# ChargerV1_0.net
KiCad netlist of a schematic drawn in EAGLE
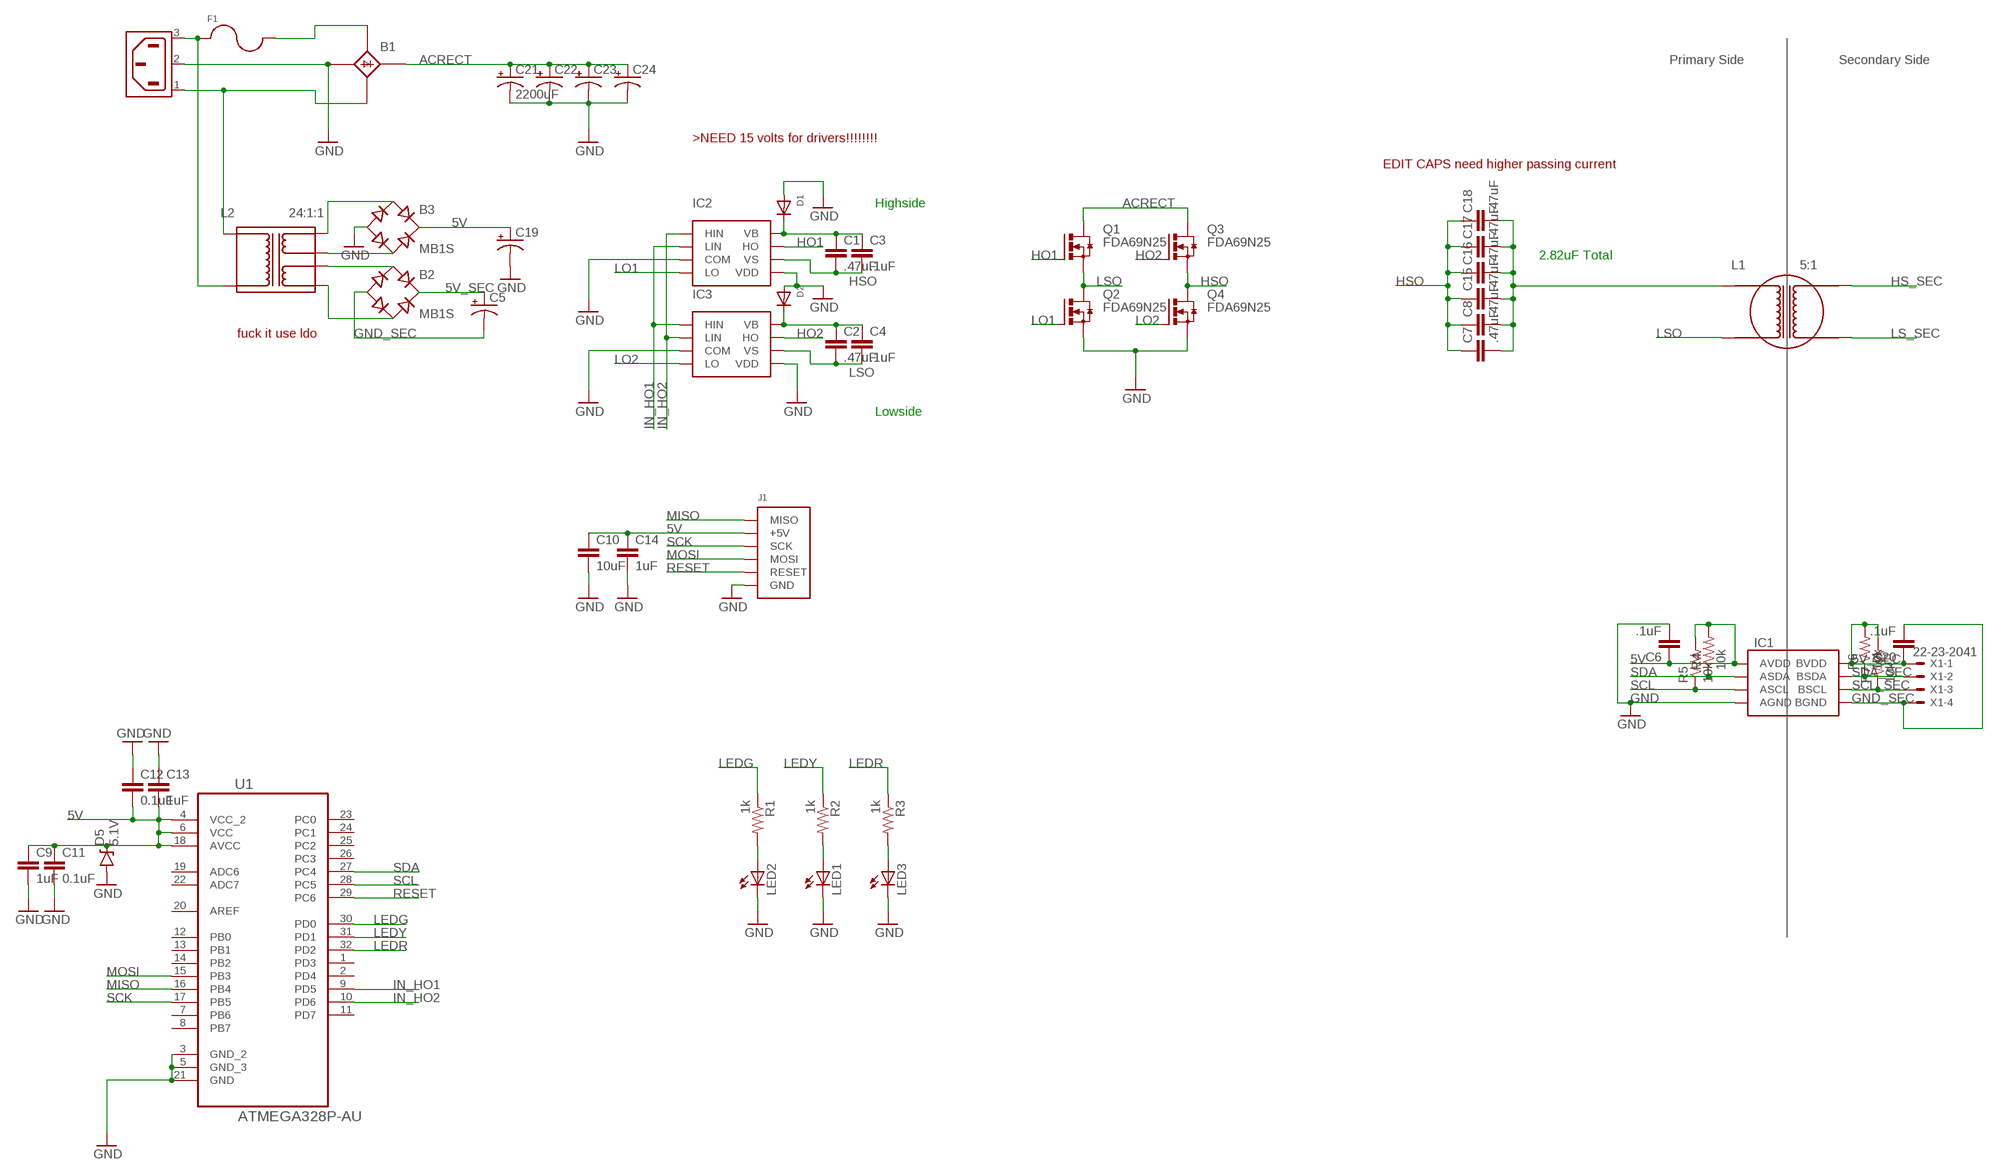
[diagram p0: schematic, sheet 1]

(export (version "E")
  (design (tool "Eeschema 10.0.6"))
  (components
    (comp (ref "B1")
      (value "B25A-")
      (footprint "eagle-import:B25A-")
      (libsource (lib "eagle-import") (part "B25A-"))
    )
    (comp (ref "B2")
      (value "MB1S")
      (footprint "eagle-import:SOIC-4")
      (libsource (lib "eagle-import") (part "MBS1"))
    )
    (comp (ref "B3")
      (value "MB1S")
      (footprint "eagle-import:SOIC-4")
      (libsource (lib "eagle-import") (part "MBS1"))
    )
    (comp (ref "C1")
      (value ".47uF")
      (footprint "eagle-import:C1206")
      (libsource (lib "eagle-import") (part "C-EUC1206"))
    )
    (comp (ref "C2")
      (value ".47uF")
      (footprint "eagle-import:C1206")
      (libsource (lib "eagle-import") (part "C-EUC1206"))
    )
    (comp (ref "C3")
      (value ".1uF")
      (footprint "eagle-import:C1206")
      (libsource (lib "eagle-import") (part "C-EUC1206"))
    )
    (comp (ref "C4")
      (value ".1uF")
      (footprint "eagle-import:C1206")
      (libsource (lib "eagle-import") (part "C-EUC1206"))
    )
    (comp (ref "C5")
      (value "CPOL-USE2.5-7")
      (footprint "eagle-import:E2,5-7")
      (libsource (lib "eagle-import") (part "CPOL-USE2.5-7"))
    )
    (comp (ref "C6")
      (value ".1uF")
      (footprint "eagle-import:0805-CAP")
      (libsource (lib "eagle-import") (part "10UF10V10%(0805)"))
    )
    (comp (ref "C7")
      (value ".47uF")
      (footprint "eagle-import:C1206")
      (libsource (lib "eagle-import") (part "C-EUC1206"))
    )
    (comp (ref "C8")
      (value ".47uF")
      (footprint "eagle-import:C1206")
      (libsource (lib "eagle-import") (part "C-EUC1206"))
    )
    (comp (ref "C9")
      (value "1uF")
      (footprint "eagle-import:0805-CAP")
      (libsource (lib "eagle-import") (part "0.33UF-50V-10%(0805)"))
    )
    (comp (ref "C10")
      (value "10uF")
      (footprint "eagle-import:0805-CAP")
      (libsource (lib "eagle-import") (part "10UF10V10%(0805)"))
    )
    (comp (ref "C11")
      (value "0.1uF")
      (footprint "eagle-import:0805-CAP")
      (libsource (lib "eagle-import") (part "0.33UF-50V-10%(0805)"))
    )
    (comp (ref "C12")
      (value "0.1uF")
      (footprint "eagle-import:0805-CAP")
      (libsource (lib "eagle-import") (part "0.33UF-50V-10%(0805)"))
    )
    (comp (ref "C13")
      (value "1uF")
      (footprint "eagle-import:0805-CAP")
      (libsource (lib "eagle-import") (part "0.33UF-50V-10%(0805)"))
    )
    (comp (ref "C14")
      (value "1uF")
      (footprint "eagle-import:0805-CAP")
      (libsource (lib "eagle-import") (part "0.33UF-50V-10%(0805)"))
    )
    (comp (ref "C15")
      (value ".47uF")
      (footprint "eagle-import:C1206")
      (libsource (lib "eagle-import") (part "C-EUC1206"))
    )
    (comp (ref "C16")
      (value ".47uF")
      (footprint "eagle-import:C1206")
      (libsource (lib "eagle-import") (part "C-EUC1206"))
    )
    (comp (ref "C17")
      (value ".47uF")
      (footprint "eagle-import:C1206")
      (libsource (lib "eagle-import") (part "C-EUC1206"))
    )
    (comp (ref "C18")
      (value ".47uF")
      (footprint "eagle-import:C1206")
      (libsource (lib "eagle-import") (part "C-EUC1206"))
    )
    (comp (ref "C19")
      (value "CPOL-USE2.5-7")
      (footprint "eagle-import:E2,5-7")
      (libsource (lib "eagle-import") (part "CPOL-USE2.5-7"))
    )
    (comp (ref "C20")
      (value ".1uF")
      (footprint "eagle-import:0805-CAP")
      (libsource (lib "eagle-import") (part "10UF10V10%(0805)"))
    )
    (comp (ref "C21")
      (value "2200uF")
      (footprint "eagle-import:EB30D")
      (libsource (lib "eagle-import") (part "CPOL-USE10-30"))
    )
    (comp (ref "C22")
      (value "CPOL-USE10-30")
      (footprint "eagle-import:EB30D")
      (libsource (lib "eagle-import") (part "CPOL-USE10-30"))
    )
    (comp (ref "C23")
      (value "CPOL-USE10-30")
      (footprint "eagle-import:EB30D")
      (libsource (lib "eagle-import") (part "CPOL-USE10-30"))
    )
    (comp (ref "C24")
      (value "CPOL-USE10-30")
      (footprint "eagle-import:EB30D")
      (libsource (lib "eagle-import") (part "CPOL-USE10-30"))
    )
    (comp (ref "D1")
      (value "DIODESMA")
      (footprint "eagle-import:SMADIODE")
      (libsource (lib "eagle-import") (part "DIODESMA"))
    )
    (comp (ref "D2")
      (value "DIODESMA")
      (footprint "eagle-import:SMADIODE")
      (libsource (lib "eagle-import") (part "DIODESMA"))
    )
    (comp (ref "D5")
      (value "5.1V")
      (footprint "eagle-import:SOD-323")
      (libsource (lib "eagle-import") (part "DIODE-ZENER5.6V"))
    )
    (comp (ref "F1")
      (value "FUSE")
      (footprint "eagle-import:FUSE_HOLDER")
      (libsource (lib "eagle-import") (part "FUSE"))
    )
    (comp (ref "IC1")
      (value "SI8600_DUALCHANNELISO")
      (footprint "eagle-import:SOIC-8")
      (libsource (lib "eagle-import") (part "SI8600_DUALCHANNELISO"))
    )
    (comp (ref "IC2")
      (value "FAN7190")
      (footprint "eagle-import:SOIC-8")
      (libsource (lib "eagle-import") (part "FAN7190"))
    )
    (comp (ref "IC3")
      (value "FAN7190")
      (footprint "eagle-import:SOIC-8")
      (libsource (lib "eagle-import") (part "FAN7190"))
    )
    (comp (ref "J1")
      (value "ISPHEADER")
      (footprint "eagle-import:2X3PIN_.1'")
      (libsource (lib "eagle-import") (part "ISPHEADER"))
    )
    (comp (ref "L1")
      (value "5:1")
      (footprint "eagle-import:TRANSFORMER_TOR_CUSTOM")
      (libsource (lib "eagle-import") (part "TRANSFORMER"))
    )
    (comp (ref "L2")
      (value "24:1:1")
      (footprint "eagle-import:TRANSFORMER_CUSTOM1")
      (libsource (lib "eagle-import") (part "TRANSFORMER1{colon}2"))
    )
    (comp (ref "LED1")
      (value "LEDCHIPLED_0805")
      (footprint "eagle-import:CHIPLED_0805")
      (libsource (lib "eagle-import") (part "LEDCHIPLED_0805"))
    )
    (comp (ref "LED2")
      (value "LEDCHIPLED_0805")
      (footprint "eagle-import:CHIPLED_0805")
      (libsource (lib "eagle-import") (part "LEDCHIPLED_0805"))
    )
    (comp (ref "LED3")
      (value "LEDCHIPLED_0805")
      (footprint "eagle-import:CHIPLED_0805")
      (libsource (lib "eagle-import") (part "LEDCHIPLED_0805"))
    )
    (comp (ref "Q1")
      (value "FDA69N25")
      (footprint "eagle-import:TO247BV")
      (libsource (lib "eagle-import") (part "IRFP240"))
    )
    (comp (ref "Q2")
      (value "FDA69N25")
      (footprint "eagle-import:TO247BV")
      (libsource (lib "eagle-import") (part "IRFP240"))
    )
    (comp (ref "Q3")
      (value "FDA69N25")
      (footprint "eagle-import:TO247BV")
      (libsource (lib "eagle-import") (part "IRFP240"))
    )
    (comp (ref "Q4")
      (value "FDA69N25")
      (footprint "eagle-import:TO247BV")
      (libsource (lib "eagle-import") (part "IRFP240"))
    )
    (comp (ref "R1")
      (value "1k")
      (footprint "eagle-import:0805")
      (libsource (lib "eagle-import") (part "0.3OHM-1/8W-1%(0805)"))
    )
    (comp (ref "R2")
      (value "1k")
      (footprint "eagle-import:0805")
      (libsource (lib "eagle-import") (part "0.3OHM-1/8W-1%(0805)"))
    )
    (comp (ref "R3")
      (value "1k")
      (footprint "eagle-import:0805")
      (libsource (lib "eagle-import") (part "0.3OHM-1/8W-1%(0805)"))
    )
    (comp (ref "R4")
      (value "10k")
      (footprint "eagle-import:0805")
      (libsource (lib "eagle-import") (part "0.3OHM-1/8W-1%(0805)"))
    )
    (comp (ref "R5")
      (value "10k")
      (footprint "eagle-import:0805")
      (libsource (lib "eagle-import") (part "0.3OHM-1/8W-1%(0805)"))
    )
    (comp (ref "R6")
      (value "10k")
      (footprint "eagle-import:0805")
      (libsource (lib "eagle-import") (part "0.3OHM-1/8W-1%(0805)"))
    )
    (comp (ref "R7")
      (value "10k")
      (footprint "eagle-import:0805")
      (libsource (lib "eagle-import") (part "0.3OHM-1/8W-1%(0805)"))
    )
    (comp (ref "U1")
      (value "ATMEGA328P-AU")
      (footprint "eagle-import:QFP80P900X900X120-32N")
      (libsource (lib "eagle-import") (part "ATMEGA328P-AU"))
    )
    (comp (ref "X1")
      (value "22-23-2041")
      (footprint "eagle-import:22-23-2041")
      (fields (field (name "MF") "MOLEX"))
      (libsource (lib "eagle-import") (part "22-23-2041"))
    )
    (comp (ref "X2")
      (value "6ESRM-P")
      (footprint "eagle-import:6ESRM-P")
      (fields (field (name "MF") "TYCO ELECTRONICS"))
      (libsource (lib "eagle-import") (part "6ESRM-P"))
    )
  )
  (nets
    (net (code "1") (name "/5V") (class "Default")
      (node (ref "B3") (pin "+") (pinfunction "+_+") (pintype "passive"))
      (node (ref "C10") (pin "1") (pinfunction "1_1") (pintype "passive"))
      (node (ref "C11") (pin "1") (pinfunction "1_1") (pintype "passive"))
      (node (ref "C12") (pin "2") (pinfunction "2_2") (pintype "passive"))
      (node (ref "C13") (pin "2") (pinfunction "2_2") (pintype "passive"))
      (node (ref "C14") (pin "1") (pinfunction "1_1") (pintype "passive"))
      (node (ref "C19") (pin "+") (pinfunction "+_+") (pintype "passive"))
      (node (ref "C6") (pin "1") (pinfunction "1_1") (pintype "passive"))
      (node (ref "C9") (pin "1") (pinfunction "1_1") (pintype "passive"))
      (node (ref "D5") (pin "C") (pinfunction "C_C") (pintype "passive"))
      (node (ref "IC1") (pin "P$1") (pinfunction "AVDD_P$1") (pintype "bidirectional"))
      (node (ref "J1") (pin "P$2") (pinfunction "+5V_P$2") (pintype "bidirectional"))
      (node (ref "R4") (pin "2") (pinfunction "2_2") (pintype "passive"))
      (node (ref "R5") (pin "2") (pinfunction "2_2") (pintype "passive"))
      (node (ref "U1") (pin "18") (pinfunction "AVCC_18") (pintype "power_in"))
      (node (ref "U1") (pin "4") (pinfunction "VCC_2_4") (pintype "power_in"))
      (node (ref "U1") (pin "6") (pinfunction "VCC_6") (pintype "power_in"))
    )
    (net (code "2") (name "/5V_SEC") (class "Default")
      (node (ref "B2") (pin "+") (pinfunction "+_+") (pintype "passive"))
      (node (ref "C20") (pin "1") (pinfunction "1_1") (pintype "passive"))
      (node (ref "C5") (pin "+") (pinfunction "+_+") (pintype "passive"))
      (node (ref "IC1") (pin "P$8") (pinfunction "BVDD_P$8") (pintype "bidirectional"))
      (node (ref "R6") (pin "2") (pinfunction "2_2") (pintype "passive"))
      (node (ref "R7") (pin "2") (pinfunction "2_2") (pintype "passive"))
      (node (ref "X1") (pin "1") (pinfunction "S_1") (pintype "passive"))
    )
    (net (code "3") (name "/ACRECT") (class "Default")
      (node (ref "B1") (pin "+1") (pinfunction "+_+1") (pintype "passive"))
      (node (ref "C21") (pin "+") (pinfunction "+_+") (pintype "passive"))
      (node (ref "C22") (pin "+") (pinfunction "+_+") (pintype "passive"))
      (node (ref "C23") (pin "+") (pinfunction "+_+") (pintype "passive"))
      (node (ref "C24") (pin "+") (pinfunction "+_+") (pintype "passive"))
      (node (ref "Q1") (pin "D") (pinfunction "D_D") (pintype "passive"))
      (node (ref "Q3") (pin "D") (pinfunction "D_D") (pintype "passive"))
    )
    (net (code "4") (name "/GND_SEC") (class "Default")
      (node (ref "B2") (pin "-") (pinfunction "-_-") (pintype "passive"))
      (node (ref "C20") (pin "2") (pinfunction "2_2") (pintype "passive"))
      (node (ref "C5") (pin "-") (pinfunction "-_-") (pintype "passive"))
      (node (ref "IC1") (pin "P$5") (pinfunction "BGND_P$5") (pintype "bidirectional"))
      (node (ref "X1") (pin "4") (pinfunction "S_4") (pintype "passive"))
    )
    (net (code "5") (name "/HO1") (class "Default")
      (node (ref "IC2") (pin "P$7") (pinfunction "HO_P$7") (pintype "bidirectional"))
      (node (ref "Q1") (pin "G") (pinfunction "G_G") (pintype "passive"))
    )
    (net (code "6") (name "/HO2") (class "Default")
      (node (ref "IC3") (pin "P$7") (pinfunction "HO_P$7") (pintype "bidirectional"))
      (node (ref "Q3") (pin "G") (pinfunction "G_G") (pintype "passive"))
    )
    (net (code "7") (name "/HSO") (class "Default")
      (node (ref "C1") (pin "2") (pinfunction "2_2") (pintype "passive"))
      (node (ref "C15") (pin "1") (pinfunction "1_1") (pintype "passive"))
      (node (ref "C16") (pin "1") (pinfunction "1_1") (pintype "passive"))
      (node (ref "C17") (pin "1") (pinfunction "1_1") (pintype "passive"))
      (node (ref "C18") (pin "1") (pinfunction "1_1") (pintype "passive"))
      (node (ref "C3") (pin "2") (pinfunction "2_2") (pintype "passive"))
      (node (ref "C7") (pin "1") (pinfunction "1_1") (pintype "passive"))
      (node (ref "C8") (pin "1") (pinfunction "1_1") (pintype "passive"))
      (node (ref "IC2") (pin "P$6") (pinfunction "VS_P$6") (pintype "bidirectional"))
      (node (ref "Q3") (pin "S") (pinfunction "S_S") (pintype "passive"))
      (node (ref "Q4") (pin "D") (pinfunction "D_D") (pintype "passive"))
    )
    (net (code "8") (name "/HS_SEC") (class "Default")
      (node (ref "L1") (pin "P$4") (pinfunction "P$4_P$4") (pintype "bidirectional"))
    )
    (net (code "9") (name "/IN_HO1") (class "Default")
      (node (ref "IC2") (pin "P$2") (pinfunction "LIN_P$2") (pintype "bidirectional"))
      (node (ref "IC3") (pin "P$1") (pinfunction "HIN_P$1") (pintype "bidirectional"))
      (node (ref "U1") (pin "9") (pinfunction "PD5_9") (pintype "bidirectional"))
    )
    (net (code "10") (name "/IN_HO2") (class "Default")
      (node (ref "IC2") (pin "P$1") (pinfunction "HIN_P$1") (pintype "bidirectional"))
      (node (ref "IC3") (pin "P$2") (pinfunction "LIN_P$2") (pintype "bidirectional"))
      (node (ref "U1") (pin "10") (pinfunction "PD6_10") (pintype "bidirectional"))
    )
    (net (code "11") (name "/LEDG") (class "Default")
      (node (ref "R1") (pin "1") (pinfunction "1_1") (pintype "passive"))
      (node (ref "U1") (pin "30") (pinfunction "PD0_30") (pintype "bidirectional"))
    )
    (net (code "12") (name "/LEDR") (class "Default")
      (node (ref "R3") (pin "1") (pinfunction "1_1") (pintype "passive"))
      (node (ref "U1") (pin "32") (pinfunction "PD2_32") (pintype "bidirectional"))
    )
    (net (code "13") (name "/LEDY") (class "Default")
      (node (ref "R2") (pin "1") (pinfunction "1_1") (pintype "passive"))
      (node (ref "U1") (pin "31") (pinfunction "PD1_31") (pintype "bidirectional"))
    )
    (net (code "14") (name "/LO1") (class "Default")
      (node (ref "IC2") (pin "P$4") (pinfunction "LO_P$4") (pintype "bidirectional"))
      (node (ref "Q2") (pin "G") (pinfunction "G_G") (pintype "passive"))
    )
    (net (code "15") (name "/LO2") (class "Default")
      (node (ref "IC3") (pin "P$4") (pinfunction "LO_P$4") (pintype "bidirectional"))
      (node (ref "Q4") (pin "G") (pinfunction "G_G") (pintype "passive"))
    )
    (net (code "16") (name "/LSO") (class "Default")
      (node (ref "C2") (pin "2") (pinfunction "2_2") (pintype "passive"))
      (node (ref "C4") (pin "2") (pinfunction "2_2") (pintype "passive"))
      (node (ref "IC3") (pin "P$6") (pinfunction "VS_P$6") (pintype "bidirectional"))
      (node (ref "L1") (pin "P$2") (pinfunction "P$2_P$2") (pintype "bidirectional"))
      (node (ref "Q1") (pin "S") (pinfunction "S_S") (pintype "passive"))
      (node (ref "Q2") (pin "D") (pinfunction "D_D") (pintype "passive"))
    )
    (net (code "17") (name "/LS_SEC") (class "Default")
      (node (ref "L1") (pin "P$3") (pinfunction "P$3_P$3") (pintype "bidirectional"))
    )
    (net (code "18") (name "/MISO") (class "Default")
      (node (ref "J1") (pin "P$1") (pinfunction "MISO_P$1") (pintype "bidirectional"))
      (node (ref "U1") (pin "16") (pinfunction "PB4_16") (pintype "bidirectional"))
    )
    (net (code "19") (name "/MOSI") (class "Default")
      (node (ref "J1") (pin "P$4") (pinfunction "MOSI_P$4") (pintype "bidirectional"))
      (node (ref "U1") (pin "15") (pinfunction "PB3_15") (pintype "bidirectional"))
    )
    (net (code "20") (name "/RESET") (class "Default")
      (node (ref "J1") (pin "P$5") (pinfunction "RESET_P$5") (pintype "bidirectional"))
      (node (ref "U1") (pin "29") (pinfunction "PC6_29") (pintype "bidirectional"))
    )
    (net (code "21") (name "/SCK") (class "Default")
      (node (ref "J1") (pin "P$3") (pinfunction "SCK_P$3") (pintype "bidirectional"))
      (node (ref "U1") (pin "17") (pinfunction "PB5_17") (pintype "bidirectional"))
    )
    (net (code "22") (name "/SCL") (class "Default")
      (node (ref "IC1") (pin "P$3") (pinfunction "ASCL_P$3") (pintype "bidirectional"))
      (node (ref "R5") (pin "1") (pinfunction "1_1") (pintype "passive"))
      (node (ref "U1") (pin "28") (pinfunction "PC5_28") (pintype "bidirectional"))
    )
    (net (code "23") (name "/SCL_SEC") (class "Default")
      (node (ref "IC1") (pin "P$6") (pinfunction "BSCL_P$6") (pintype "bidirectional"))
      (node (ref "R7") (pin "1") (pinfunction "1_1") (pintype "passive"))
      (node (ref "X1") (pin "3") (pinfunction "S_3") (pintype "passive"))
    )
    (net (code "24") (name "/SDA") (class "Default")
      (node (ref "IC1") (pin "P$2") (pinfunction "ASDA_P$2") (pintype "bidirectional"))
      (node (ref "R4") (pin "1") (pinfunction "1_1") (pintype "passive"))
      (node (ref "U1") (pin "27") (pinfunction "PC4_27") (pintype "bidirectional"))
    )
    (net (code "25") (name "/SDA_SEC") (class "Default")
      (node (ref "IC1") (pin "P$7") (pinfunction "BSDA_P$7") (pintype "bidirectional"))
      (node (ref "R6") (pin "1") (pinfunction "1_1") (pintype "passive"))
      (node (ref "X1") (pin "2") (pinfunction "S_2") (pintype "passive"))
    )
    (net (code "26") (name "GND") (class "Default")
      (node (ref "B1") (pin "-1") (pinfunction "-_-1") (pintype "passive"))
      (node (ref "B3") (pin "-") (pinfunction "-_-") (pintype "passive"))
      (node (ref "C10") (pin "2") (pinfunction "2_2") (pintype "passive"))
      (node (ref "C11") (pin "2") (pinfunction "2_2") (pintype "passive"))
      (node (ref "C12") (pin "1") (pinfunction "1_1") (pintype "passive"))
      (node (ref "C13") (pin "1") (pinfunction "1_1") (pintype "passive"))
      (node (ref "C14") (pin "2") (pinfunction "2_2") (pintype "passive"))
      (node (ref "C19") (pin "-") (pinfunction "-_-") (pintype "passive"))
      (node (ref "C21") (pin "-") (pinfunction "-_-") (pintype "passive"))
      (node (ref "C22") (pin "-") (pinfunction "-_-") (pintype "passive"))
      (node (ref "C23") (pin "-") (pinfunction "-_-") (pintype "passive"))
      (node (ref "C24") (pin "-") (pinfunction "-_-") (pintype "passive"))
      (node (ref "C6") (pin "2") (pinfunction "2_2") (pintype "passive"))
      (node (ref "C9") (pin "2") (pinfunction "2_2") (pintype "passive"))
      (node (ref "D1") (pin "A") (pinfunction "A_A") (pintype "passive"))
      (node (ref "D2") (pin "A") (pinfunction "A_A") (pintype "passive"))
      (node (ref "D5") (pin "A") (pinfunction "A_A") (pintype "passive"))
      (node (ref "IC1") (pin "P$4") (pinfunction "AGND_P$4") (pintype "bidirectional"))
      (node (ref "IC2") (pin "P$3") (pinfunction "COM_P$3") (pintype "bidirectional"))
      (node (ref "IC2") (pin "P$5") (pinfunction "VDD_P$5") (pintype "bidirectional"))
      (node (ref "IC3") (pin "P$3") (pinfunction "COM_P$3") (pintype "bidirectional"))
      (node (ref "IC3") (pin "P$5") (pinfunction "VDD_P$5") (pintype "bidirectional"))
      (node (ref "J1") (pin "P$6") (pinfunction "GND_P$6") (pintype "bidirectional"))
      (node (ref "LED1") (pin "C") (pinfunction "C_C") (pintype "passive"))
      (node (ref "LED2") (pin "C") (pinfunction "C_C") (pintype "passive"))
      (node (ref "LED3") (pin "C") (pinfunction "C_C") (pintype "passive"))
      (node (ref "Q2") (pin "S") (pinfunction "S_S") (pintype "passive"))
      (node (ref "Q4") (pin "S") (pinfunction "S_S") (pintype "passive"))
      (node (ref "U1") (pin "21") (pinfunction "GND_21") (pintype "passive"))
      (node (ref "U1") (pin "3") (pinfunction "GND_2_3") (pintype "passive"))
      (node (ref "U1") (pin "5") (pinfunction "GND_3_5") (pintype "passive"))
      (node (ref "X2") (pin "2") (pinfunction "SH_2") (pintype "passive"))
    )
    (net (code "27") (name "Net-(B1-AC1-PadAC1-)") (class "Default")
      (node (ref "B1") (pin "AC1-") (pinfunction "AC1_AC1-") (pintype "passive"))
      (node (ref "F1") (pin "P$3") (pinfunction "P$2_P$3") (pintype "bidirectional"))
      (node (ref "F1") (pin "P$4") (pinfunction "P$2_P$4") (pintype "bidirectional"))
    )
    (net (code "28") (name "Net-(B2-AC1)") (class "Default")
      (node (ref "B2") (pin "~1") (pinfunction "AC1_~1") (pintype "passive"))
      (node (ref "L2") (pin "OUT21") (pinfunction "OUT21_OUT21") (pintype "bidirectional"))
    )
    (net (code "29") (name "Net-(B2-AC2)") (class "Default")
      (node (ref "B2") (pin "~2") (pinfunction "AC2_~2") (pintype "passive"))
      (node (ref "L2") (pin "OUT22") (pinfunction "OUT22_OUT22") (pintype "bidirectional"))
    )
    (net (code "30") (name "Net-(B3-AC1)") (class "Default")
      (node (ref "B3") (pin "~1") (pinfunction "AC1_~1") (pintype "passive"))
      (node (ref "L2") (pin "OUT11") (pinfunction "OUT11_OUT11") (pintype "bidirectional"))
    )
    (net (code "31") (name "Net-(B3-AC2)") (class "Default")
      (node (ref "B3") (pin "~2") (pinfunction "AC2_~2") (pintype "passive"))
      (node (ref "L2") (pin "OUT12") (pinfunction "OUT12_OUT12") (pintype "bidirectional"))
    )
    (net (code "32") (name "Net-(C15-Pad2)") (class "Default")
      (node (ref "C15") (pin "2") (pinfunction "2_2") (pintype "passive"))
      (node (ref "C16") (pin "2") (pinfunction "2_2") (pintype "passive"))
      (node (ref "C17") (pin "2") (pinfunction "2_2") (pintype "passive"))
      (node (ref "C18") (pin "2") (pinfunction "2_2") (pintype "passive"))
      (node (ref "C7") (pin "2") (pinfunction "2_2") (pintype "passive"))
      (node (ref "C8") (pin "2") (pinfunction "2_2") (pintype "passive"))
      (node (ref "L1") (pin "P$1") (pinfunction "P$1_P$1") (pintype "bidirectional"))
    )
    (net (code "33") (name "Net-(IC2-VB)") (class "Default")
      (node (ref "C1") (pin "1") (pinfunction "1_1") (pintype "passive"))
      (node (ref "C3") (pin "1") (pinfunction "1_1") (pintype "passive"))
      (node (ref "D1") (pin "C") (pinfunction "C_C") (pintype "passive"))
      (node (ref "IC2") (pin "P$8") (pinfunction "VB_P$8") (pintype "bidirectional"))
    )
    (net (code "34") (name "Net-(IC3-VB)") (class "Default")
      (node (ref "C2") (pin "1") (pinfunction "1_1") (pintype "passive"))
      (node (ref "C4") (pin "1") (pinfunction "1_1") (pintype "passive"))
      (node (ref "D2") (pin "C") (pinfunction "C_C") (pintype "passive"))
      (node (ref "IC3") (pin "P$8") (pinfunction "VB_P$8") (pintype "bidirectional"))
    )
    (net (code "35") (name "Net-(LED1-PadA)") (class "Default")
      (node (ref "LED1") (pin "A") (pinfunction "A_A") (pintype "passive"))
      (node (ref "R2") (pin "2") (pinfunction "2_2") (pintype "passive"))
    )
    (net (code "36") (name "Net-(LED2-PadA)") (class "Default")
      (node (ref "LED2") (pin "A") (pinfunction "A_A") (pintype "passive"))
      (node (ref "R1") (pin "2") (pinfunction "2_2") (pintype "passive"))
    )
    (net (code "37") (name "Net-(LED3-PadA)") (class "Default")
      (node (ref "LED3") (pin "A") (pinfunction "A_A") (pintype "passive"))
      (node (ref "R3") (pin "2") (pinfunction "2_2") (pintype "passive"))
    )
    (net (code "38") (name "Net-(X2-AC1)") (class "Default")
      (node (ref "B1") (pin "AC2-") (pinfunction "AC2_AC2-") (pintype "passive"))
      (node (ref "L2") (pin "IN1") (pinfunction "IN1_IN1") (pintype "bidirectional"))
      (node (ref "X2") (pin "1") (pinfunction "AC1_1") (pintype "passive"))
    )
    (net (code "39") (name "Net-(X2-AC2)") (class "Default")
      (node (ref "F1") (pin "P$1") (pinfunction "P$1_P$1") (pintype "bidirectional"))
      (node (ref "F1") (pin "P$2") (pinfunction "P$1_P$2") (pintype "bidirectional"))
      (node (ref "L2") (pin "IN2") (pinfunction "IN2_IN2") (pintype "bidirectional"))
      (node (ref "X2") (pin "3") (pinfunction "AC2_3") (pintype "passive"))
    )
    (net (code "40") (name "unconnected-(B1-Pad+)") (class "Default")
      (node (ref "B1") (pin "+") (pinfunction "+_+") (pintype "passive"))
    )
    (net (code "41") (name "unconnected-(B1-Pad-)") (class "Default")
      (node (ref "B1") (pin "-") (pinfunction "-_-") (pintype "passive"))
    )
    (net (code "42") (name "unconnected-(B1-PadAC1)") (class "Default")
      (node (ref "B1") (pin "AC1") (pinfunction "AC1_AC1") (pintype "passive"))
    )
    (net (code "43") (name "unconnected-(B1-PadAC2)") (class "Default")
      (node (ref "B1") (pin "AC2") (pinfunction "AC2_AC2") (pintype "passive"))
    )
    (net (code "44") (name "unconnected-(U1-ADC6-Pad19)") (class "Default")
      (node (ref "U1") (pin "19") (pinfunction "ADC6_19") (pintype "input"))
    )
    (net (code "45") (name "unconnected-(U1-ADC7-Pad22)") (class "Default")
      (node (ref "U1") (pin "22") (pinfunction "ADC7_22") (pintype "input"))
    )
    (net (code "46") (name "unconnected-(U1-AREF-Pad20)") (class "Default")
      (node (ref "U1") (pin "20") (pinfunction "AREF_20") (pintype "input"))
    )
    (net (code "47") (name "unconnected-(U1-PB0-Pad12)") (class "Default")
      (node (ref "U1") (pin "12") (pinfunction "PB0_12") (pintype "bidirectional"))
    )
    (net (code "48") (name "unconnected-(U1-PB1-Pad13)") (class "Default")
      (node (ref "U1") (pin "13") (pinfunction "PB1_13") (pintype "bidirectional"))
    )
    (net (code "49") (name "unconnected-(U1-PB2-Pad14)") (class "Default")
      (node (ref "U1") (pin "14") (pinfunction "PB2_14") (pintype "bidirectional"))
    )
    (net (code "50") (name "unconnected-(U1-PB6-Pad7)") (class "Default")
      (node (ref "U1") (pin "7") (pinfunction "PB6_7") (pintype "bidirectional"))
    )
    (net (code "51") (name "unconnected-(U1-PB7-Pad8)") (class "Default")
      (node (ref "U1") (pin "8") (pinfunction "PB7_8") (pintype "bidirectional"))
    )
    (net (code "52") (name "unconnected-(U1-PC0-Pad23)") (class "Default")
      (node (ref "U1") (pin "23") (pinfunction "PC0_23") (pintype "bidirectional"))
    )
    (net (code "53") (name "unconnected-(U1-PC1-Pad24)") (class "Default")
      (node (ref "U1") (pin "24") (pinfunction "PC1_24") (pintype "bidirectional"))
    )
    (net (code "54") (name "unconnected-(U1-PC2-Pad25)") (class "Default")
      (node (ref "U1") (pin "25") (pinfunction "PC2_25") (pintype "bidirectional"))
    )
    (net (code "55") (name "unconnected-(U1-PC3-Pad26)") (class "Default")
      (node (ref "U1") (pin "26") (pinfunction "PC3_26") (pintype "bidirectional"))
    )
    (net (code "56") (name "unconnected-(U1-PD3-Pad1)") (class "Default")
      (node (ref "U1") (pin "1") (pinfunction "PD3_1") (pintype "bidirectional"))
    )
    (net (code "57") (name "unconnected-(U1-PD4-Pad2)") (class "Default")
      (node (ref "U1") (pin "2") (pinfunction "PD4_2") (pintype "bidirectional"))
    )
    (net (code "58") (name "unconnected-(U1-PD7-Pad11)") (class "Default")
      (node (ref "U1") (pin "11") (pinfunction "PD7_11") (pintype "bidirectional"))
    )
  )
)
